# STM32_Controller.net
KiCad netlist of a schematic drawn in Altium Designer
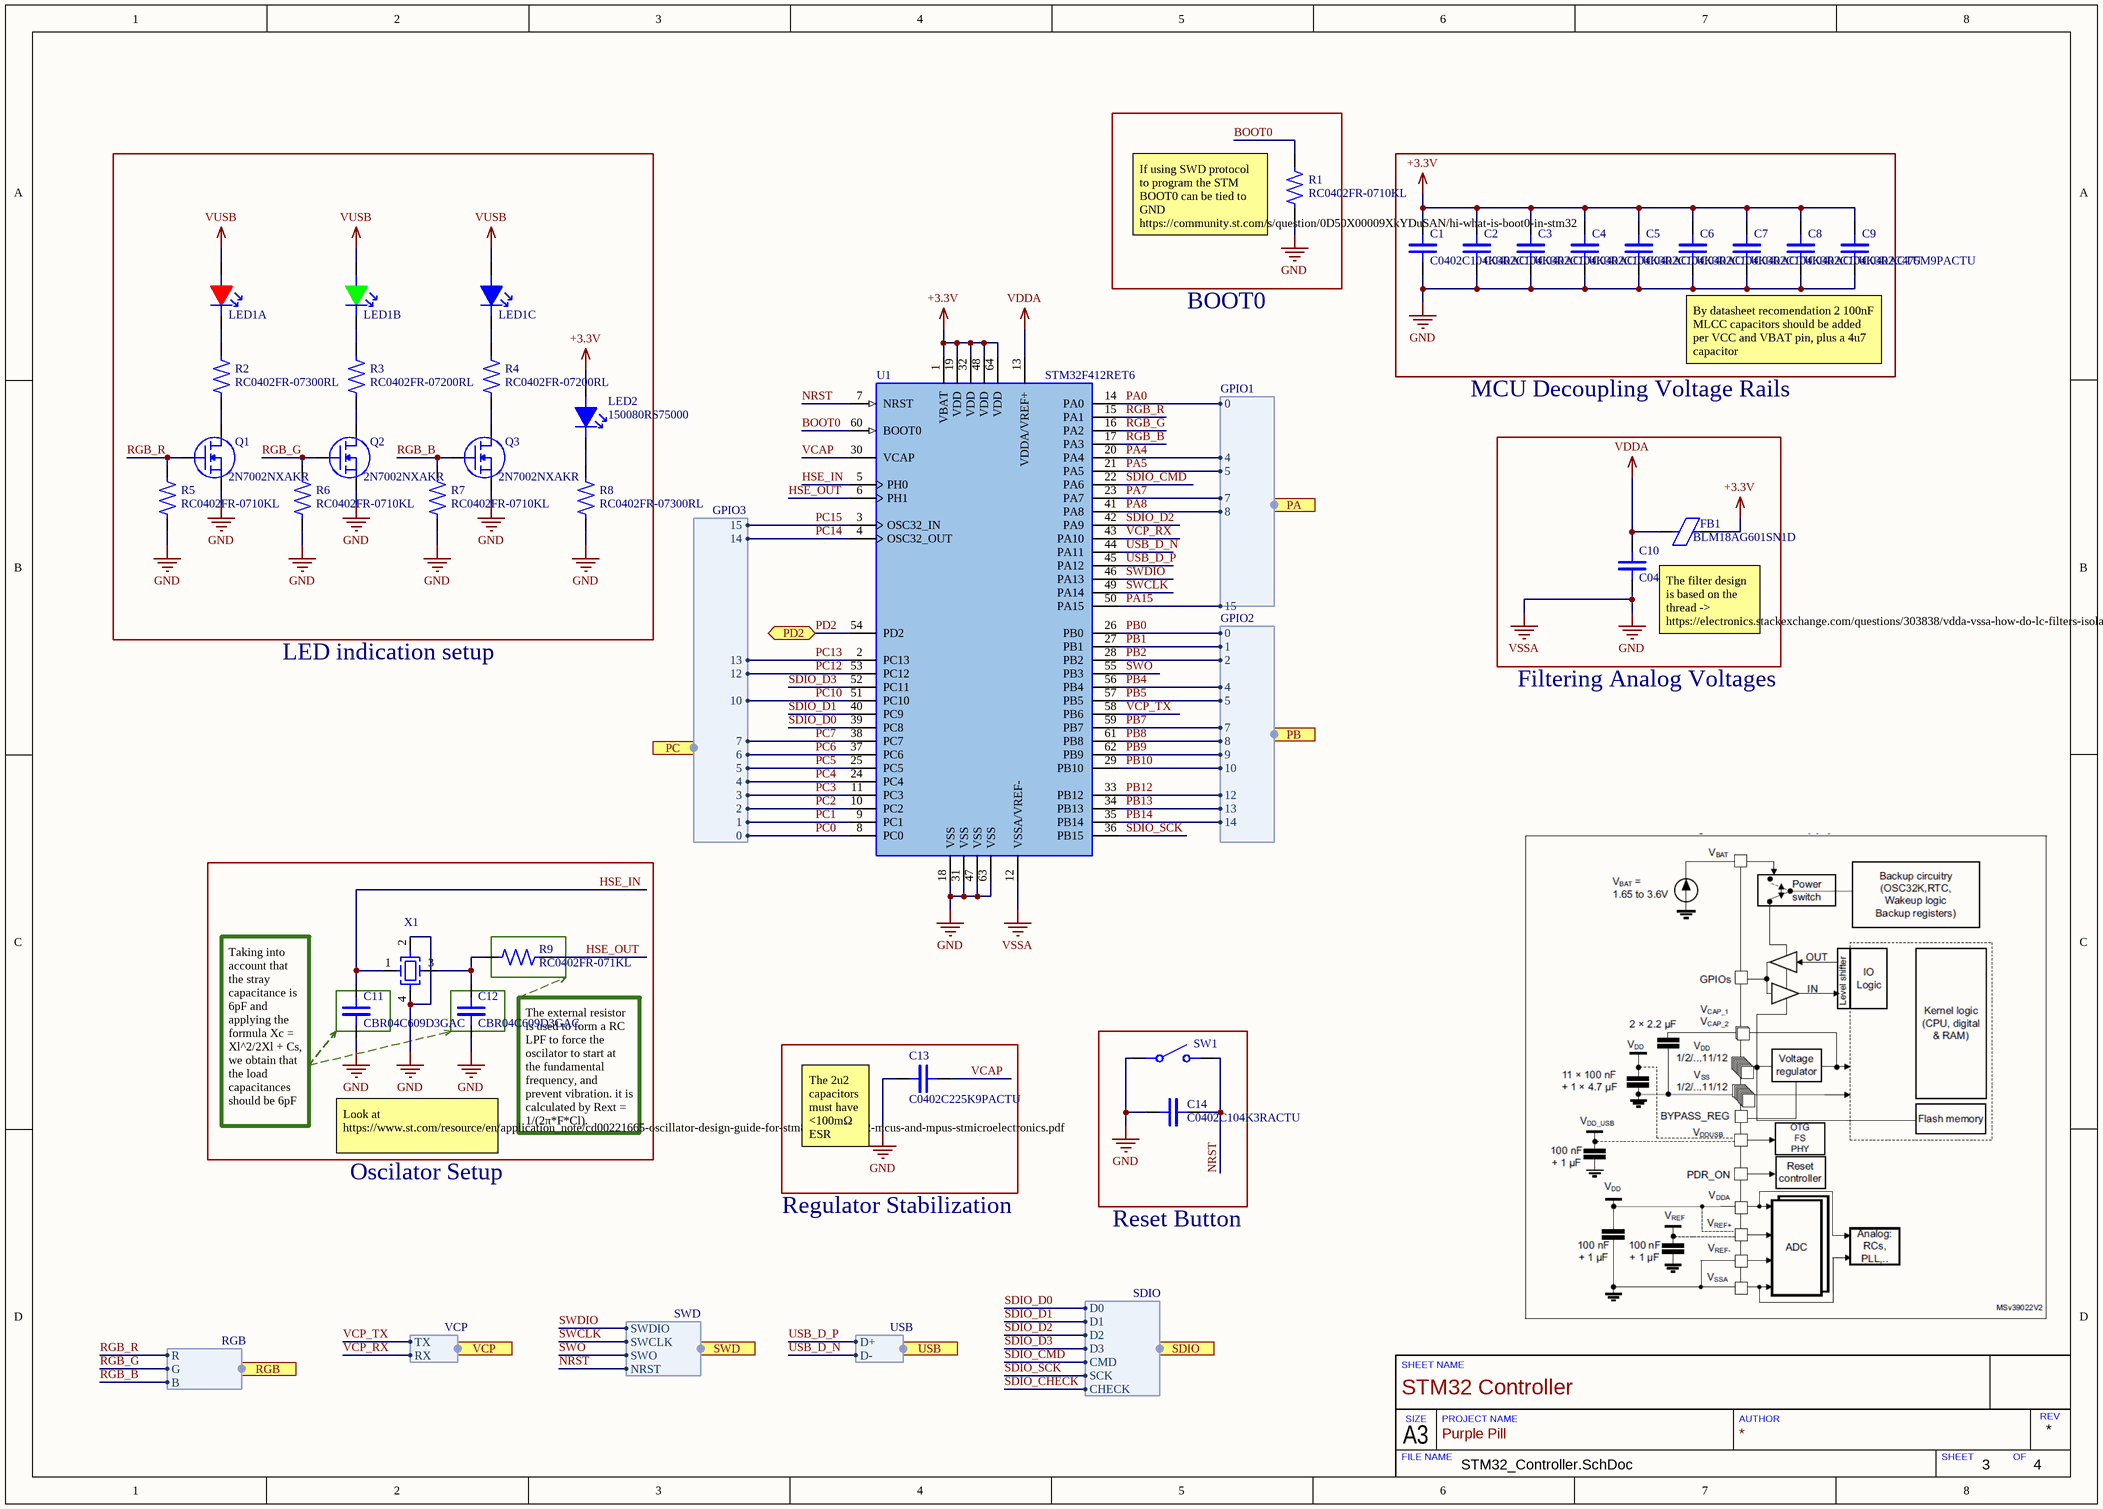
[diagram p0: STM32_Controller.SchDoc]

(export (version "E")
  (design (tool "Eeschema 10.0.6"))
  (components
    (comp (ref "C1")
      (value "C0402C104K3RACTU")
      (footprint "CM0402_KEMET")
      (description "0.1 µF ±10% 25V Ceramic Capacitor X7R 0402 (1005 Metric")
      (fields (field (name "MANUFACTURER") "KEMET") (field (name "TOLERANCE") "10%"))
      (libsource (lib "STAR UC3M") (part "Non-polar capacitor"))
    )
    (comp (ref "C2")
      (value "C0402C104K3RACTU")
      (footprint "CM0402_KEMET")
      (description "0.1 µF ±10% 25V Ceramic Capacitor X7R 0402 (1005 Metric")
      (fields (field (name "MANUFACTURER") "KEMET") (field (name "TOLERANCE") "10%"))
      (libsource (lib "STAR UC3M") (part "Non-polar capacitor"))
    )
    (comp (ref "C3")
      (value "C0402C104K3RACTU")
      (footprint "CM0402_KEMET")
      (description "0.1 µF ±10% 25V Ceramic Capacitor X7R 0402 (1005 Metric")
      (fields (field (name "MANUFACTURER") "KEMET") (field (name "TOLERANCE") "10%"))
      (libsource (lib "STAR UC3M") (part "Non-polar capacitor"))
    )
    (comp (ref "C4")
      (value "C0402C104K3RACTU")
      (footprint "CM0402_KEMET")
      (description "0.1 µF ±10% 25V Ceramic Capacitor X7R 0402 (1005 Metric")
      (fields (field (name "MANUFACTURER") "KEMET") (field (name "TOLERANCE") "10%"))
      (libsource (lib "STAR UC3M") (part "Non-polar capacitor"))
    )
    (comp (ref "C5")
      (value "C0402C104K3RACTU")
      (footprint "CM0402_KEMET")
      (description "0.1 µF ±10% 25V Ceramic Capacitor X7R 0402 (1005 Metric")
      (fields (field (name "MANUFACTURER") "KEMET") (field (name "TOLERANCE") "10%"))
      (libsource (lib "STAR UC3M") (part "Non-polar capacitor"))
    )
    (comp (ref "C6")
      (value "C0402C104K3RACTU")
      (footprint "CM0402_KEMET")
      (description "0.1 µF ±10% 25V Ceramic Capacitor X7R 0402 (1005 Metric")
      (fields (field (name "MANUFACTURER") "KEMET") (field (name "TOLERANCE") "10%"))
      (libsource (lib "STAR UC3M") (part "Non-polar capacitor"))
    )
    (comp (ref "C7")
      (value "C0402C104K3RACTU")
      (footprint "CM0402_KEMET")
      (description "0.1 µF ±10% 25V Ceramic Capacitor X7R 0402 (1005 Metric")
      (fields (field (name "MANUFACTURER") "KEMET") (field (name "TOLERANCE") "10%"))
      (libsource (lib "STAR UC3M") (part "Non-polar capacitor"))
    )
    (comp (ref "C8")
      (value "C0402C104K3RACTU")
      (footprint "CM0402_KEMET")
      (description "0.1 µF ±10% 25V Ceramic Capacitor X7R 0402 (1005 Metric")
      (fields (field (name "MANUFACTURER") "KEMET") (field (name "TOLERANCE") "10%"))
      (libsource (lib "STAR UC3M") (part "Non-polar capacitor"))
    )
    (comp (ref "C9")
      (value "C0402C475M9PACTU")
      (footprint "CM0402_KEMET")
      (description "4.7 µF ±20% 6.3V Ceramic Capacitor X5R 0402 (1005 Metric)")
      (fields (field (name "MANUFACTURER") "KEMET") (field (name "TOLERANCE") "10%"))
      (libsource (lib "STAR UC3M") (part "Non-polar capacitor"))
    )
    (comp (ref "C10")
      (value "C0402C104K3RACTU")
      (footprint "CM0402_KEMET")
      (description "0.1 µF ±10% 25V Ceramic Capacitor X7R 0402 (1005 Metric")
      (fields (field (name "MANUFACTURER") "KEMET") (field (name "TOLERANCE") "10%"))
      (libsource (lib "STAR UC3M") (part "Non-polar capacitor"))
    )
    (comp (ref "C11")
      (value "CBR04C609D3GAC")
      (footprint "CM0402_KEMET")
      (description "6 pF ±0.5pF 25V Ceramic Capacitor C0G, NP0 0402 (1005 Metric)")
      (fields (field (name "MANUFACTURER") "KEMET") (field (name "TOLERANCE") "8.3%"))
      (libsource (lib "STAR UC3M") (part "Non-polar capacitor"))
    )
    (comp (ref "C12")
      (value "CBR04C609D3GAC")
      (footprint "CM0402_KEMET")
      (description "6 pF ±0.5pF 25V Ceramic Capacitor C0G, NP0 0402 (1005 Metric)")
      (fields (field (name "MANUFACTURER") "KEMET") (field (name "TOLERANCE") "8.3%"))
      (libsource (lib "STAR UC3M") (part "Non-polar capacitor"))
    )
    (comp (ref "C13")
      (value "C0402C225K9PACTU")
      (footprint "CM0402_KEMET")
      (description "2.2 µF ±10% 6.3V Ceramic Capacitor X5R 0402 (1005 Metric)")
      (fields (field (name "MANUFACTURER") "KEMET") (field (name "TOLERANCE") "10%"))
      (libsource (lib "") (part "Non-polar capacitor_2"))
    )
    (comp (ref "C14")
      (value "C0402C104K3RACTU")
      (footprint "CM0402_KEMET")
      (description "0.1 µF ±10% 25V Ceramic Capacitor X7R 0402 (1005 Metric")
      (fields (field (name "MANUFACTURER") "KEMET") (field (name "TOLERANCE") "10%"))
      (libsource (lib "") (part "Non-polar capacitor_1"))
    )
    (comp (ref "FB1")
      (value "BLM18AG601SN1D")
      (footprint "FB0603_MURATA")
      (description "Ferrite Chip, 1 Function(s), 0.5A, 2 Pin(s)")
      (fields (field (name "MANUFACTURER") "Murata") (field (name "TOLERANCE") "25%"))
      (libsource (lib "STAR UC3M") (part "Ferrite Bead"))
    )
    (comp (ref "LED1")
      (value "TC5050RGBF08-3CJH-AF53A")
      (footprint "LED_RGB_5050")
      (description "20mA -40℃~+85℃ RGB 200mW 5050(mm) Light Emitting Diodes (LED) ROHS")
      (fields (field (name "MANUFACTURER") "TCWIN") (field (name "LCSC PART#") "C784540"))
      (libsource (lib "STAR UC3M") (part "LED RGB"))
    )
    (comp (ref "LED2")
      (value "150080RS75000")
      (footprint "LED0805_WURTH")
      (description "Red 625nm LED Indication - Discrete 2V 0805 (2012 Metric)")
      (fields (field (name "MANUFACTURER") "Würth Elektronik") (field (name "LCSC PART#") "C5137314"))
      (libsource (lib "STAR UC3M") (part "LED"))
    )
    (comp (ref "Q1")
      (value "2N7002NXAKR")
      (footprint "SOT23-3")
      (description "2N7002NXAK - 60 V, single N-channel Trench MOSFET")
      (fields (field (name "MANUFACTURER") "Nexperia") (field (name "LCSC PART#") "C350313"))
      (libsource (lib "STAR UC3M") (part "MOSFET enh N-channel"))
    )
    (comp (ref "Q2")
      (value "2N7002NXAKR")
      (footprint "SOT23-3")
      (description "2N7002NXAK - 60 V, single N-channel Trench MOSFET")
      (fields (field (name "MANUFACTURER") "Nexperia") (field (name "LCSC PART#") "C350313"))
      (libsource (lib "STAR UC3M") (part "MOSFET enh N-channel"))
    )
    (comp (ref "Q3")
      (value "2N7002NXAKR")
      (footprint "SOT23-3")
      (description "2N7002NXAK - 60 V, single N-channel Trench MOSFET")
      (fields (field (name "MANUFACTURER") "Nexperia") (field (name "LCSC PART#") "C350313"))
      (libsource (lib "STAR UC3M") (part "MOSFET enh N-channel"))
    )
    (comp (ref "R1")
      (value "RC0402FR-0710KL")
      (footprint "R0402_YAGEO")
      (description "10 kOhms ±1% 0.063W, 1/16W Chip Resistor 0402 (1005 Metric) Moisture Resistant Thick Film")
      (fields (field (name "TOLERANCE") "1%") (field (name "MANUFACTURER") "YAGEO"))
      (libsource (lib "STAR UC3M") (part "Resistor"))
    )
    (comp (ref "R2")
      (value "RC0402FR-07300RL")
      (footprint "R0402_YAGEO")
      (description "300 Ohms ±1% 0.063W, 1/16W Chip Resistor 0402 (1005 Metric) Moisture Resistant Thick Film")
      (fields (field (name "TOLERANCE") "1%") (field (name "MANUFACTURER") "YAGEO"))
      (libsource (lib "STAR UC3M") (part "Resistor"))
    )
    (comp (ref "R3")
      (value "RC0402FR-07200RL")
      (footprint "R0402_YAGEO")
      (description "200 Ohms ±1% 0.063W, 1/16W Chip Resistor 0402 (1005 Metric) Moisture Resistant Thick Film")
      (fields (field (name "TOLERANCE") "1%") (field (name "MANUFACTURER") "YAGEO"))
      (libsource (lib "STAR UC3M") (part "Resistor"))
    )
    (comp (ref "R4")
      (value "RC0402FR-07200RL")
      (footprint "R0402_YAGEO")
      (description "200 Ohms ±1% 0.063W, 1/16W Chip Resistor 0402 (1005 Metric) Moisture Resistant Thick Film")
      (fields (field (name "TOLERANCE") "1%") (field (name "MANUFACTURER") "YAGEO"))
      (libsource (lib "STAR UC3M") (part "Resistor"))
    )
    (comp (ref "R5")
      (value "RC0402FR-0710KL")
      (footprint "R0402_YAGEO")
      (description "10 kOhms ±1% 0.063W, 1/16W Chip Resistor 0402 (1005 Metric) Moisture Resistant Thick Film")
      (fields (field (name "TOLERANCE") "1%") (field (name "MANUFACTURER") "YAGEO"))
      (libsource (lib "STAR UC3M") (part "Resistor"))
    )
    (comp (ref "R6")
      (value "RC0402FR-0710KL")
      (footprint "R0402_YAGEO")
      (description "10 kOhms ±1% 0.063W, 1/16W Chip Resistor 0402 (1005 Metric) Moisture Resistant Thick Film")
      (fields (field (name "TOLERANCE") "1%") (field (name "MANUFACTURER") "YAGEO"))
      (libsource (lib "STAR UC3M") (part "Resistor"))
    )
    (comp (ref "R7")
      (value "RC0402FR-0710KL")
      (footprint "R0402_YAGEO")
      (description "10 kOhms ±1% 0.063W, 1/16W Chip Resistor 0402 (1005 Metric) Moisture Resistant Thick Film")
      (fields (field (name "TOLERANCE") "1%") (field (name "MANUFACTURER") "YAGEO"))
      (libsource (lib "STAR UC3M") (part "Resistor"))
    )
    (comp (ref "R8")
      (value "RC0402FR-07300RL")
      (footprint "R0402_YAGEO")
      (description "300 Ohms ±1% 0.063W, 1/16W Chip Resistor 0402 (1005 Metric) Moisture Resistant Thick Film")
      (fields (field (name "TOLERANCE") "1%") (field (name "MANUFACTURER") "YAGEO"))
      (libsource (lib "STAR UC3M") (part "Resistor"))
    )
    (comp (ref "R9")
      (value "RC0402FR-071KL")
      (footprint "R0402_YAGEO")
      (description "1 kOhms ±1% 0.063W, 1/16W Chip Resistor 0402 (1005 Metric) Moisture Resistant Thick Film")
      (fields (field (name "TOLERANCE") "1%") (field (name "MANUFACTURER") "YAGEO"))
      (libsource (lib "STAR UC3M") (part "Resistor"))
    )
    (comp (ref "SW1")
      (value "Push button SPST small")
      (footprint "1TS002E-2400-2500-CT")
      (fields
        (field (name "MANUFACTURER") "HYP")
        (field (name "VOLTAGE") "12V")
        (field (name "LCSC PART#") "C319365")
      )
      (libsource (lib "STAR UC3M") (part "SPST Switch"))
    )
    (comp (ref "U1")
      (value "STM32F412RET6")
      (footprint "LQFP64")
      (description "RISC Microcontroller, 32-Bit, FLASH, CORTEX-M4 CPU, 100MHz, CMOS, PQFP64")
      (fields (field (name "MANUFACTURER") "STMicroelectronics") (field (name "LCSC PART#") "C89374"))
      (libsource (lib "STAR UC3M") (part "STM32F412RET6"))
    )
    (comp (ref "X1")
      (value "CR24MHz")
      (footprint "XTAL_3.2x2.4")
      (description "Crystal Oscillator 24MHz 9pF +/-10ppm +/-20ppm")
      (fields (field (name "MANUFACTURER") "ECS") (field (name "TOLERANCE") "10 PPM"))
      (libsource (lib "STAR UC3M") (part "Crystal Oscilator with GND"))
    )
  )
  (nets
    (net (code "9") (name "+3.3V") (class "Default")
      (node (ref "C1") (pin "2") (pinfunction "2_2") (pintype "passive"))
      (node (ref "C2") (pin "2") (pinfunction "2_2") (pintype "passive"))
      (node (ref "C3") (pin "2") (pinfunction "2_2") (pintype "passive"))
      (node (ref "C4") (pin "2") (pinfunction "2_2") (pintype "passive"))
      (node (ref "C5") (pin "2") (pinfunction "2_2") (pintype "passive"))
      (node (ref "C6") (pin "2") (pinfunction "2_2") (pintype "passive"))
      (node (ref "C7") (pin "2") (pinfunction "2_2") (pintype "passive"))
      (node (ref "C8") (pin "2") (pinfunction "2_2") (pintype "passive"))
      (node (ref "C9") (pin "2") (pinfunction "2_2") (pintype "passive"))
      (node (ref "FB1") (pin "2") (pinfunction "2_2") (pintype "passive"))
      (node (ref "LED2") (pin "2") (pinfunction "Anode_2") (pintype "passive"))
      (node (ref "U1") (pin "1") (pinfunction "VBAT_1") (pintype "power_in"))
      (node (ref "U1") (pin "19") (pinfunction "VDD_19") (pintype "power_in"))
      (node (ref "U1") (pin "32") (pinfunction "VDD_32") (pintype "power_in"))
      (node (ref "U1") (pin "48") (pinfunction "VDD_48") (pintype "power_in"))
      (node (ref "U1") (pin "64") (pinfunction "VDD_64") (pintype "power_in"))
    )
    (net (code "10") (name "/BOOT0") (class "Default")
      (node (ref "R1") (pin "2") (pinfunction "2_2") (pintype "passive"))
      (node (ref "U1") (pin "60") (pinfunction "BOOT0_60") (pintype "input"))
    )
    (net (code "11") (name "/HSE_IN") (class "Default")
      (node (ref "C11") (pin "2") (pinfunction "2_2") (pintype "passive"))
      (node (ref "U1") (pin "5") (pinfunction "PH0_5") (pintype "passive"))
      (node (ref "X1") (pin "1") (pinfunction "XTAL1_1") (pintype "passive"))
    )
    (net (code "12") (name "/HSE_OUT") (class "Default")
      (node (ref "R9") (pin "2") (pinfunction "2_2") (pintype "passive"))
      (node (ref "U1") (pin "6") (pinfunction "PH1_6") (pintype "passive"))
    )
    (net (code "13") (name "/NRST") (class "Default")
      (node (ref "C14") (pin "2") (pinfunction "2_2") (pintype "passive"))
      (node (ref "SW1") (pin "1") (pinfunction "1_1") (pintype "passive"))
      (node (ref "U1") (pin "7") (pinfunction "NRST_7") (pintype "input"))
    )
    (net (code "14") (name "/PA0") (class "Default")
      (node (ref "U1") (pin "14") (pinfunction "PA0_14") (pintype "passive"))
    )
    (net (code "15") (name "/PA4") (class "Default")
      (node (ref "U1") (pin "20") (pinfunction "PA4_20") (pintype "passive"))
    )
    (net (code "16") (name "/PA5") (class "Default")
      (node (ref "U1") (pin "21") (pinfunction "PA5_21") (pintype "passive"))
    )
    (net (code "17") (name "/PA7") (class "Default")
      (node (ref "U1") (pin "23") (pinfunction "PA7_23") (pintype "passive"))
    )
    (net (code "18") (name "/PA8") (class "Default")
      (node (ref "U1") (pin "41") (pinfunction "PA8_41") (pintype "passive"))
    )
    (net (code "19") (name "/PA15") (class "Default")
      (node (ref "U1") (pin "50") (pinfunction "PA15_50") (pintype "passive"))
    )
    (net (code "20") (name "/PB0") (class "Default")
      (node (ref "U1") (pin "26") (pinfunction "PB0_26") (pintype "passive"))
    )
    (net (code "21") (name "/PB1") (class "Default")
      (node (ref "U1") (pin "27") (pinfunction "PB1_27") (pintype "passive"))
    )
    (net (code "22") (name "/PB2") (class "Default")
      (node (ref "U1") (pin "28") (pinfunction "PB2_28") (pintype "passive"))
    )
    (net (code "23") (name "/PB4") (class "Default")
      (node (ref "U1") (pin "56") (pinfunction "PB4_56") (pintype "passive"))
    )
    (net (code "24") (name "/PB5") (class "Default")
      (node (ref "U1") (pin "57") (pinfunction "PB5_57") (pintype "passive"))
    )
    (net (code "25") (name "/PB7") (class "Default")
      (node (ref "U1") (pin "59") (pinfunction "PB7_59") (pintype "passive"))
    )
    (net (code "26") (name "/PB8") (class "Default")
      (node (ref "U1") (pin "61") (pinfunction "PB8_61") (pintype "passive"))
    )
    (net (code "27") (name "/PB9") (class "Default")
      (node (ref "U1") (pin "62") (pinfunction "PB9_62") (pintype "passive"))
    )
    (net (code "28") (name "/PB10") (class "Default")
      (node (ref "U1") (pin "29") (pinfunction "PB10_29") (pintype "passive"))
    )
    (net (code "29") (name "/PB12") (class "Default")
      (node (ref "U1") (pin "33") (pinfunction "PB12_33") (pintype "passive"))
    )
    (net (code "30") (name "/PB13") (class "Default")
      (node (ref "U1") (pin "34") (pinfunction "PB13_34") (pintype "passive"))
    )
    (net (code "31") (name "/PB14") (class "Default")
      (node (ref "U1") (pin "35") (pinfunction "PB14_35") (pintype "passive"))
    )
    (net (code "32") (name "/PC0") (class "Default")
      (node (ref "U1") (pin "8") (pinfunction "PC0_8") (pintype "passive"))
    )
    (net (code "33") (name "/PC1") (class "Default")
      (node (ref "U1") (pin "9") (pinfunction "PC1_9") (pintype "passive"))
    )
    (net (code "34") (name "/PC2") (class "Default")
      (node (ref "U1") (pin "10") (pinfunction "PC2_10") (pintype "passive"))
    )
    (net (code "35") (name "/PC3") (class "Default")
      (node (ref "U1") (pin "11") (pinfunction "PC3_11") (pintype "passive"))
    )
    (net (code "36") (name "/PC4") (class "Default")
      (node (ref "U1") (pin "24") (pinfunction "PC4_24") (pintype "passive"))
    )
    (net (code "37") (name "/PC5") (class "Default")
      (node (ref "U1") (pin "25") (pinfunction "PC5_25") (pintype "passive"))
    )
    (net (code "38") (name "/PC6") (class "Default")
      (node (ref "U1") (pin "37") (pinfunction "PC6_37") (pintype "passive"))
    )
    (net (code "39") (name "/PC7") (class "Default")
      (node (ref "U1") (pin "38") (pinfunction "PC7_38") (pintype "passive"))
    )
    (net (code "40") (name "/PC10") (class "Default")
      (node (ref "U1") (pin "51") (pinfunction "PC10_51") (pintype "passive"))
    )
    (net (code "41") (name "/PC12") (class "Default")
      (node (ref "U1") (pin "53") (pinfunction "PC12_53") (pintype "passive"))
    )
    (net (code "42") (name "/PC13") (class "Default")
      (node (ref "U1") (pin "2") (pinfunction "PC13_2") (pintype "passive"))
    )
    (net (code "43") (name "/PC14") (class "Default")
      (node (ref "U1") (pin "4") (pinfunction "OSC32_OUT_4") (pintype "passive"))
    )
    (net (code "44") (name "/PC15") (class "Default")
      (node (ref "U1") (pin "3") (pinfunction "OSC32_IN_3") (pintype "passive"))
    )
    (net (code "45") (name "/PD2") (class "Default")
      (node (ref "U1") (pin "54") (pinfunction "PD2_54") (pintype "passive"))
    )
    (net (code "46") (name "/RGB_B") (class "Default")
      (node (ref "Q3") (pin "1") (pinfunction "Gate_1") (pintype "passive"))
      (node (ref "R7") (pin "2") (pinfunction "2_2") (pintype "passive"))
      (node (ref "U1") (pin "17") (pinfunction "PA3_17") (pintype "passive"))
    )
    (net (code "47") (name "/RGB_G") (class "Default")
      (node (ref "Q2") (pin "1") (pinfunction "Gate_1") (pintype "passive"))
      (node (ref "R6") (pin "2") (pinfunction "2_2") (pintype "passive"))
      (node (ref "U1") (pin "16") (pinfunction "PA2_16") (pintype "passive"))
    )
    (net (code "48") (name "/RGB_R") (class "Default")
      (node (ref "Q1") (pin "1") (pinfunction "Gate_1") (pintype "passive"))
      (node (ref "R5") (pin "2") (pinfunction "2_2") (pintype "passive"))
      (node (ref "U1") (pin "15") (pinfunction "PA1_15") (pintype "passive"))
    )
    (net (code "50") (name "/SDIO_CMD") (class "Default")
      (node (ref "U1") (pin "22") (pinfunction "PA6_22") (pintype "passive"))
    )
    (net (code "51") (name "/SDIO_D0") (class "Default")
      (node (ref "U1") (pin "39") (pinfunction "PC8_39") (pintype "passive"))
    )
    (net (code "52") (name "/SDIO_D1") (class "Default")
      (node (ref "U1") (pin "40") (pinfunction "PC9_40") (pintype "passive"))
    )
    (net (code "53") (name "/SDIO_D2") (class "Default")
      (node (ref "U1") (pin "42") (pinfunction "PA9_42") (pintype "passive"))
    )
    (net (code "54") (name "/SDIO_D3") (class "Default")
      (node (ref "U1") (pin "52") (pinfunction "PC11_52") (pintype "passive"))
    )
    (net (code "55") (name "/SDIO_SCK") (class "Default")
      (node (ref "U1") (pin "36") (pinfunction "PB15_36") (pintype "passive"))
    )
    (net (code "56") (name "/SWCLK") (class "Default")
      (node (ref "U1") (pin "49") (pinfunction "PA14_49") (pintype "passive"))
    )
    (net (code "57") (name "/SWDIO") (class "Default")
      (node (ref "U1") (pin "46") (pinfunction "PA13_46") (pintype "passive"))
    )
    (net (code "58") (name "/SWO") (class "Default")
      (node (ref "U1") (pin "55") (pinfunction "PB3_55") (pintype "passive"))
    )
    (net (code "59") (name "/USB_D_N") (class "Default")
      (node (ref "U1") (pin "44") (pinfunction "PA11_44") (pintype "passive"))
    )
    (net (code "60") (name "/USB_D_P") (class "Default")
      (node (ref "U1") (pin "45") (pinfunction "PA12_45") (pintype "passive"))
    )
    (net (code "61") (name "/VCAP") (class "Default")
      (node (ref "C13") (pin "1") (pinfunction "1_1") (pintype "passive"))
      (node (ref "U1") (pin "30") (pinfunction "VCAP_30") (pintype "passive"))
    )
    (net (code "62") (name "/VCP_RX") (class "Default")
      (node (ref "U1") (pin "43") (pinfunction "PA10_43") (pintype "passive"))
    )
    (net (code "63") (name "/VCP_TX") (class "Default")
      (node (ref "U1") (pin "58") (pinfunction "PB6_58") (pintype "passive"))
    )
    (net (code "72") (name "GND") (class "Default")
      (node (ref "C1") (pin "1") (pinfunction "1_1") (pintype "passive"))
      (node (ref "C10") (pin "1") (pinfunction "1_1") (pintype "passive"))
      (node (ref "C11") (pin "1") (pinfunction "1_1") (pintype "passive"))
      (node (ref "C12") (pin "1") (pinfunction "1_1") (pintype "passive"))
      (node (ref "C13") (pin "2") (pinfunction "2_2") (pintype "passive"))
      (node (ref "C14") (pin "1") (pinfunction "1_1") (pintype "passive"))
      (node (ref "C2") (pin "1") (pinfunction "1_1") (pintype "passive"))
      (node (ref "C3") (pin "1") (pinfunction "1_1") (pintype "passive"))
      (node (ref "C4") (pin "1") (pinfunction "1_1") (pintype "passive"))
      (node (ref "C5") (pin "1") (pinfunction "1_1") (pintype "passive"))
      (node (ref "C6") (pin "1") (pinfunction "1_1") (pintype "passive"))
      (node (ref "C7") (pin "1") (pinfunction "1_1") (pintype "passive"))
      (node (ref "C8") (pin "1") (pinfunction "1_1") (pintype "passive"))
      (node (ref "C9") (pin "1") (pinfunction "1_1") (pintype "passive"))
      (node (ref "Q1") (pin "3") (pinfunction "Source_3") (pintype "passive"))
      (node (ref "Q2") (pin "3") (pinfunction "Source_3") (pintype "passive"))
      (node (ref "Q3") (pin "3") (pinfunction "Source_3") (pintype "passive"))
      (node (ref "R1") (pin "1") (pinfunction "1_1") (pintype "passive"))
      (node (ref "R5") (pin "1") (pinfunction "1_1") (pintype "passive"))
      (node (ref "R6") (pin "1") (pinfunction "1_1") (pintype "passive"))
      (node (ref "R7") (pin "1") (pinfunction "1_1") (pintype "passive"))
      (node (ref "R8") (pin "1") (pinfunction "1_1") (pintype "passive"))
      (node (ref "SW1") (pin "2") (pinfunction "2_2") (pintype "passive"))
      (node (ref "U1") (pin "12") (pinfunction "VSSA/VREF-_12") (pintype "power_in"))
      (node (ref "U1") (pin "18") (pinfunction "VSS_18") (pintype "power_in"))
      (node (ref "U1") (pin "31") (pinfunction "VSS_31") (pintype "power_in"))
      (node (ref "U1") (pin "47") (pinfunction "VSS_47") (pintype "power_in"))
      (node (ref "U1") (pin "63") (pinfunction "VSS_63") (pintype "power_in"))
      (node (ref "X1") (pin "2") (pinfunction "Ground_2") (pintype "passive"))
      (node (ref "X1") (pin "4") (pinfunction "Ground_4") (pintype "passive"))
    )
    (net (code "73") (name "Net-(LED1A-Cathode1)") (class "Default")
      (node (ref "LED1") (pin "2") (pinfunction "Cathode1_2") (pintype "passive"))
      (node (ref "R2") (pin "2") (pinfunction "2_2") (pintype "passive"))
    )
    (net (code "74") (name "Net-(LED1B-Cathode2)") (class "Default")
      (node (ref "LED1") (pin "4") (pinfunction "Cathode2_4") (pintype "passive"))
      (node (ref "R3") (pin "2") (pinfunction "2_2") (pintype "passive"))
    )
    (net (code "75") (name "Net-(LED1C-Cathode3)") (class "Default")
      (node (ref "LED1") (pin "6") (pinfunction "Cathode3_6") (pintype "passive"))
      (node (ref "R4") (pin "2") (pinfunction "2_2") (pintype "passive"))
    )
    (net (code "76") (name "Net-(LED2-Cathode)") (class "Default")
      (node (ref "LED2") (pin "1") (pinfunction "Cathode_1") (pintype "passive"))
      (node (ref "R8") (pin "2") (pinfunction "2_2") (pintype "passive"))
    )
    (net (code "77") (name "Net-(Q1-Drain)") (class "Default")
      (node (ref "Q1") (pin "2") (pinfunction "Drain_2") (pintype "passive"))
      (node (ref "R2") (pin "1") (pinfunction "1_1") (pintype "passive"))
    )
    (net (code "78") (name "Net-(Q2-Drain)") (class "Default")
      (node (ref "Q2") (pin "2") (pinfunction "Drain_2") (pintype "passive"))
      (node (ref "R3") (pin "1") (pinfunction "1_1") (pintype "passive"))
    )
    (net (code "79") (name "Net-(Q3-Drain)") (class "Default")
      (node (ref "Q3") (pin "2") (pinfunction "Drain_2") (pintype "passive"))
      (node (ref "R4") (pin "1") (pinfunction "1_1") (pintype "passive"))
    )
    (net (code "80") (name "Net-(X1-XTAL2)") (class "Default")
      (node (ref "C12") (pin "2") (pinfunction "2_2") (pintype "passive"))
      (node (ref "R9") (pin "1") (pinfunction "1_1") (pintype "passive"))
      (node (ref "X1") (pin "3") (pinfunction "XTAL2_3") (pintype "passive"))
    )
    (net (code "81") (name "VDDA") (class "Default")
      (node (ref "C10") (pin "2") (pinfunction "2_2") (pintype "passive"))
      (node (ref "FB1") (pin "1") (pinfunction "1_1") (pintype "passive"))
      (node (ref "U1") (pin "13") (pinfunction "VDDA/VREF+_13") (pintype "power_in"))
    )
    (net (code "82") (name "VUSB") (class "Default")
      (node (ref "LED1") (pin "1") (pinfunction "Anode1_1") (pintype "passive"))
      (node (ref "LED1") (pin "3") (pinfunction "Anode2_3") (pintype "passive"))
      (node (ref "LED1") (pin "5") (pinfunction "Anode3_5") (pintype "passive"))
    )
  )
)
